# Power_ascii.net
KiCad netlist of a schematic drawn in Altium Designer
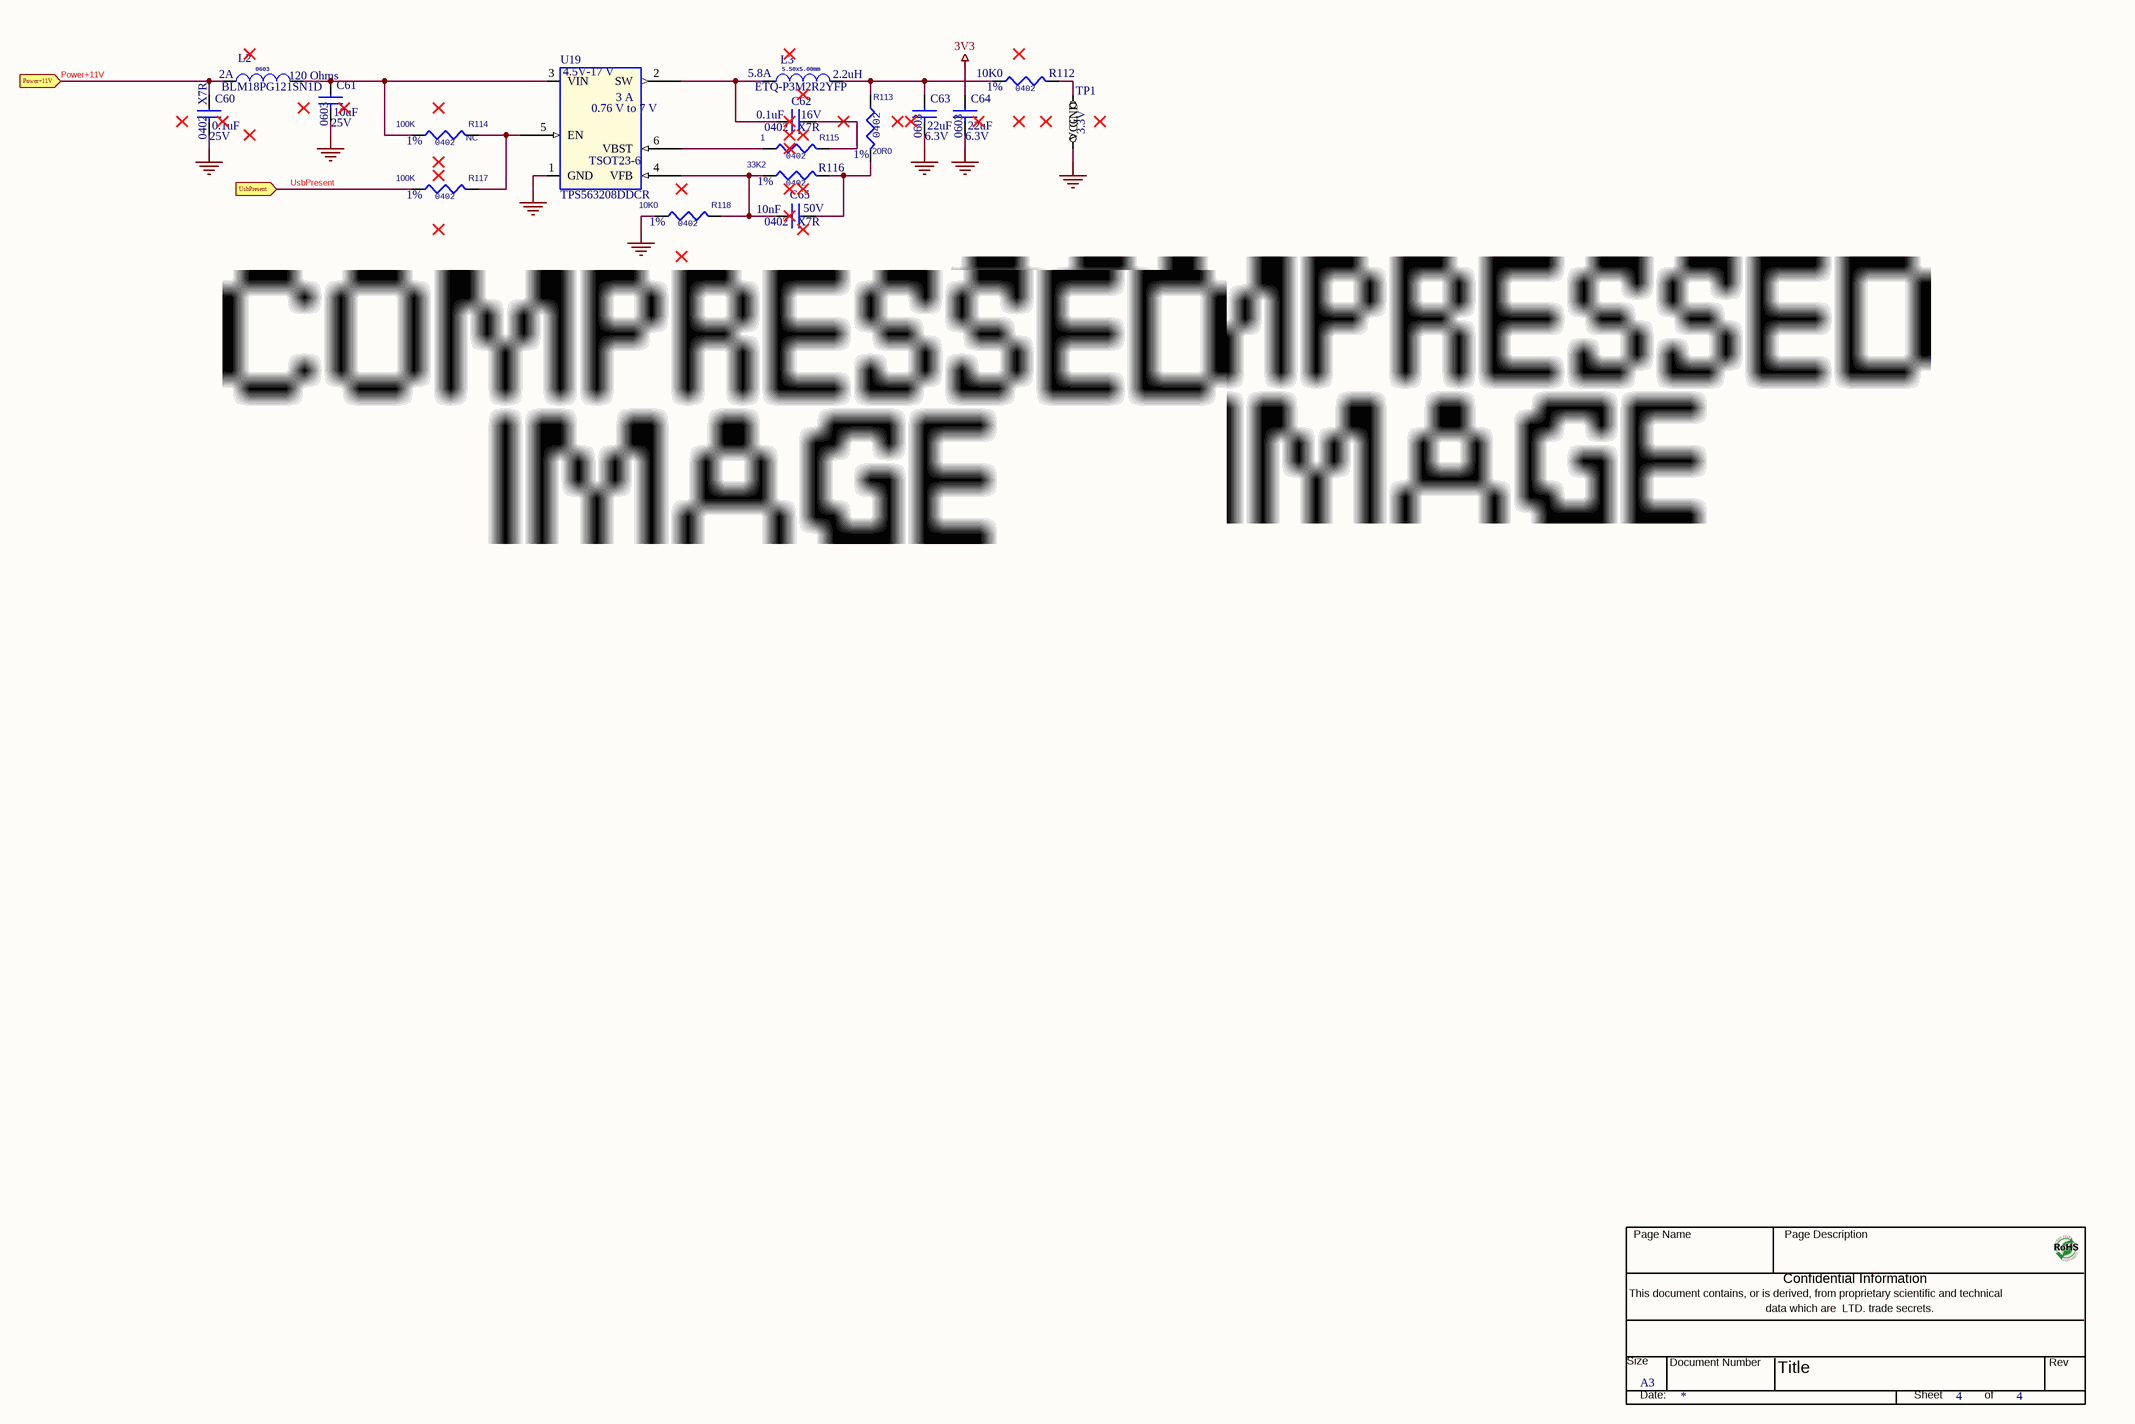
[diagram p0: Power_ascii.SchDoc]

(export (version "E")
  (design (tool "Eeschema 10.0.6"))
  (components
    (comp (ref "*")
      (value "MobulusTitleBlockBlank")
      (fields
        (field (name "PAGE SIZE") "A3")
        (field (name "PAGE NUMBER") "4")
        (field (name "PAGE COUNT") "4")
      )
      (libsource (lib "*") (part "MobulusTitleBlockBlank"))
    )
    (comp (ref "C60")
      (value "0.1uF")
      (footprint "0402")
      (description "CAP CER 0.1UF 25V X7R 0402")
      (fields
        (field (name "MFG") "Murata Electronics")
        (field (name "PCBFOOTPRINT") "0402")
        (field (name "PART NUMBER") "GRM155R71E104KE14D")
        (field (name "TYPE") "X7R")
        (field (name "VOLTAGE") "25V")
      )
      (libsource (lib "*") (part "CAP0402_0.1uF 25V"))
    )
    (comp (ref "C61")
      (value "10uF")
      (footprint "0603")
      (description "CAP CER 10UF 25V X5R 0603")
      (fields
        (field (name "VOLTAGE") "25V")
        (field (name "PART NUMBER") "CL10A106MA8NRNC")
        (field (name "PCBFOOTPRINT") "0603")
        (field (name "MFG") "Samsung Electro-Mechanics")
      )
      (libsource (lib "*") (part "CAP0603_10uF 25V"))
    )
    (comp (ref "C62")
      (value "0.1uF")
      (footprint "0402")
      (description "CAP_CER_0.1uF_16V_X7R_0402")
      (fields
        (field (name "VOLTAGE") "16V")
        (field (name "PART NUMBER") "CC0402KRX7R7BB104")
        (field (name "PCBFOOTPRINT") "0402   X7R")
        (field (name "MFG") "Yageo")
      )
      (libsource (lib "*") (part "CAP0402_0.1uF 16V"))
    )
    (comp (ref "C63")
      (value "22uF")
      (footprint "0603")
      (description "CAP CER 22UF 6.3V X6S 0603")
      (fields
        (field (name "MFG") "Murata Electronics")
        (field (name "PCBFOOTPRINT") "0603")
        (field (name "PART NUMBER") "GRM188C80J226ME15D")
        (field (name "VOLTAGE") "6.3V")
      )
      (libsource (lib "*") (part "CAP0603_22uF 6.3V"))
    )
    (comp (ref "C64")
      (value "22uF")
      (footprint "0603")
      (description "CAP CER 22UF 6.3V X6S 0603")
      (fields
        (field (name "MFG") "Murata Electronics")
        (field (name "PCBFOOTPRINT") "0603")
        (field (name "PART NUMBER") "GRM188C80J226ME15D")
        (field (name "VOLTAGE") "6.3V")
      )
      (libsource (lib "*") (part "CAP0603_22uF 6.3V"))
    )
    (comp (ref "C65")
      (value "10nF")
      (footprint "0402")
      (description "CAP CER 10000PF 50V X7R 0402")
      (fields
        (field (name "MFG") "Samsung Electro-Mechanics")
        (field (name "PCBFOOTPRINT") "0402   X7R")
        (field (name "PART NUMBER") "CL05B103KB5NNNC")
        (field (name "VOLTAGE") "50V")
      )
      (libsource (lib "*") (part "CAP0402_10nF 50V"))
    )
    (comp (ref "L2")
      (value "BLM18PG121SN1D")
      (footprint "L0603")
      (description "EMI Suppression filter 2A")
      (fields
        (field (name "MFG") "Murata Electronics")
        (field (name "IMPEDANCE") "120 Ohms")
        (field (name "CURRENT") "2A")
      )
      (libsource (lib "*") (part "BLM18PG121SN1D"))
    )
    (comp (ref "L3")
      (value "ETQ-P3M2R2YFP")
      (footprint "ETQ-P3M2R2YFP")
      (description "FIXED IND 2.2UH 5.8A 24.8 MOHM")
      (fields
        (field (name "INDUCTANCE") "2.2uH")
        (field (name "CURRENT") "5.8A")
        (field (name "MFG") "Panasonic Electronic Components")
      )
      (libsource (lib "*") (part "ETQ-P3M2R2YFP 2.2uH 5.8A"))
    )
    (comp (ref "R112")
      (value "10K0")
      (footprint "0402")
      (description "RES SMD 10K OHM 1% 1/16W 0402")
      (fields
        (field (name "TOLERANCE") "1%")
        (field (name "POWER") "1/16W")
        (field (name "PART NUMBER") "RC0402FR-0710KL")
      )
      (libsource (lib "*") (part "R0402_10K0_1%"))
    )
    (comp (ref "R113")
      (value "20R0")
      (footprint "0402")
      (description "RES SMD 20 OHM 1% 1/16W 0402")
      (fields
        (field (name "TOLERANCE") "1%")
        (field (name "POWER") "1/16W")
        (field (name "PART NUMBER") "RC0402FR-0720RL")
      )
      (libsource (lib "*") (part "R0402_20R0_1%"))
    )
    (comp (ref "R114")
      (value "100K")
      (footprint "0402")
      (description "RES SMD 100K OHM 1% 1/16W 0402")
      (fields
        (field (name "TOLERANCE") "1%")
        (field (name "POWER") "1/16W")
        (field (name "PART NUMBER") "RC0402FR-07100KL")
        (field (name "ASSY") "NC")
      )
      (libsource (lib "*") (part "R0402_100K_1%"))
    )
    (comp (ref "R115")
      (value "1")
      (footprint "0402")
      (description "RES SMD 1R0 5% 1/16W 0402")
      (fields (field (name "POWER") "1/16W") (field (name "PART NUMBER") "CRGCQ0402J1R0"))
      (libsource (lib "*") (part "R0402_1R_5%"))
    )
    (comp (ref "R116")
      (value "33K2")
      (footprint "0402")
      (description "RES 33K2 1% 1/16W 0402")
      (fields
        (field (name "TOLERANCE") "1%")
        (field (name "POWER") "1/16W")
        (field (name "PART NUMBER") "RMCF0402FT33K2")
      )
      (libsource (lib "*") (part "R0402_33K2_1%"))
    )
    (comp (ref "R117")
      (value "100K")
      (footprint "0402")
      (description "RES SMD 100K OHM 1% 1/16W 0402")
      (fields
        (field (name "TOLERANCE") "1%")
        (field (name "POWER") "1/16W")
        (field (name "PART NUMBER") "RC0402FR-07100KL")
      )
      (libsource (lib "*") (part "R0402_100K_1%"))
    )
    (comp (ref "R118")
      (value "10K0")
      (footprint "0402")
      (description "RES SMD 10K OHM 1% 1/16W 0402")
      (fields
        (field (name "TOLERANCE") "1%")
        (field (name "POWER") "1/16W")
        (field (name "PART NUMBER") "RC0402FR-0710KL")
      )
      (libsource (lib "*") (part "R0402_10K0_1%"))
    )
    (comp (ref "TP1")
      (value "TP Power 2 5mm")
      (footprint "jump2_th5mm")
      (description "CONN HEADER VERT 2POS 5MM")
      (fields
        (field (name "PART NUMBER") "M20-9990246")
        (field (name "MFG") "Harwin Inc.")
        (field (name "LABEL") "3.3V")
      )
      (libsource (lib "*") (part "TP Power 2 5mm"))
    )
    (comp (ref "U19")
      (value "TPS563208DDCR")
      (footprint "TSOT23-6_TPS563208DDCR")
      (description "IC REG BUCK ADJ 3A TSOT23-6")
      (fields
        (field (name "CURRENT") "3 A")
        (field (name "MFG") "Texas Instruments")
        (field (name "OUT_VOLTAGE") "0.76 V to 7 V")
        (field (name "PCBFOOTPRINT") "TSOT23-6")
        (field (name "VOLTAGE") "4.5V-17 V")
      )
      (libsource (lib "*") (part "TPS563208DDCR"))
    )
  )
  (nets
    (net (code "1") (name "/Power+11V") (class "Default")
      (node (ref "C60") (pin "1") (pinfunction "1_1") (pintype "passive"))
      (node (ref "L2") (pin "1") (pinfunction "1_1") (pintype "passive"))
    )
    (net (code "2") (name "/UsbPresent") (class "Default")
      (node (ref "R117") (pin "1") (pinfunction "1_1") (pintype "passive"))
    )
    (net (code "3") (name "3V3") (class "Default")
      (node (ref "C64") (pin "1") (pinfunction "1_1") (pintype "passive"))
    )
    (net (code "4") (name "GND") (class "Default")
      (node (ref "C60") (pin "2") (pinfunction "2_2") (pintype "passive"))
      (node (ref "C61") (pin "2") (pinfunction "2_2") (pintype "passive"))
      (node (ref "C63") (pin "2") (pinfunction "2_2") (pintype "passive"))
      (node (ref "C64") (pin "2") (pinfunction "2_2") (pintype "passive"))
      (node (ref "R118") (pin "1") (pinfunction "1_1") (pintype "passive"))
      (node (ref "TP1") (pin "2") (pinfunction "GND_2") (pintype "passive"))
      (node (ref "U19") (pin "1") (pinfunction "GND_1") (pintype "power_in"))
    )
    (net (code "5") (name "Net-(C62-Pad2)") (class "Default")
      (node (ref "C62") (pin "2") (pinfunction "2_2") (pintype "passive"))
      (node (ref "R115") (pin "2") (pinfunction "2_2") (pintype "passive"))
    )
    (net (code "6") (name "Net-(C63-Pad1)") (class "Default")
      (node (ref "C63") (pin "1") (pinfunction "1_1") (pintype "passive"))
      (node (ref "L3") (pin "2") (pinfunction "2_2") (pintype "passive"))
      (node (ref "R112") (pin "1") (pinfunction "1_1") (pintype "passive"))
      (node (ref "R113") (pin "1") (pinfunction "1_1") (pintype "passive"))
    )
    (net (code "7") (name "Net-(C65-Pad2)") (class "Default")
      (node (ref "C65") (pin "2") (pinfunction "2_2") (pintype "passive"))
      (node (ref "R113") (pin "2") (pinfunction "2_2") (pintype "passive"))
      (node (ref "R116") (pin "2") (pinfunction "2_2") (pintype "passive"))
    )
    (net (code "8") (name "Net-(TP1-VCC)") (class "Default")
      (node (ref "R112") (pin "2") (pinfunction "2_2") (pintype "passive"))
      (node (ref "TP1") (pin "1") (pinfunction "VCC_1") (pintype "passive"))
    )
    (net (code "9") (name "Net-(U19-EN)") (class "Default")
      (node (ref "R114") (pin "2") (pinfunction "2_2") (pintype "passive"))
      (node (ref "R117") (pin "2") (pinfunction "2_2") (pintype "passive"))
      (node (ref "U19") (pin "5") (pinfunction "EN_5") (pintype "input"))
    )
    (net (code "10") (name "Net-(U19-SW)") (class "Default")
      (node (ref "C62") (pin "1") (pinfunction "1_1") (pintype "passive"))
      (node (ref "L3") (pin "1") (pinfunction "1_1") (pintype "passive"))
      (node (ref "U19") (pin "2") (pinfunction "SW_2") (pintype "output"))
    )
    (net (code "11") (name "Net-(U19-VBST)") (class "Default")
      (node (ref "R115") (pin "1") (pinfunction "1_1") (pintype "passive"))
      (node (ref "U19") (pin "6") (pinfunction "VBST_6") (pintype "input"))
    )
    (net (code "12") (name "Net-(U19-VFB)") (class "Default")
      (node (ref "C65") (pin "1") (pinfunction "1_1") (pintype "passive"))
      (node (ref "R116") (pin "1") (pinfunction "1_1") (pintype "passive"))
      (node (ref "R118") (pin "2") (pinfunction "2_2") (pintype "passive"))
      (node (ref "U19") (pin "4") (pinfunction "VFB_4") (pintype "input"))
    )
    (net (code "13") (name "Net-(U19-VIN)") (class "Default")
      (node (ref "C61") (pin "1") (pinfunction "1_1") (pintype "passive"))
      (node (ref "L2") (pin "2") (pinfunction "2_2") (pintype "passive"))
      (node (ref "R114") (pin "1") (pinfunction "1_1") (pintype "passive"))
      (node (ref "U19") (pin "3") (pinfunction "VIN_3") (pintype "power_in"))
    )
  )
)
